# AnalogSigCond.net
KiCad netlist of a schematic drawn in Altium Designer
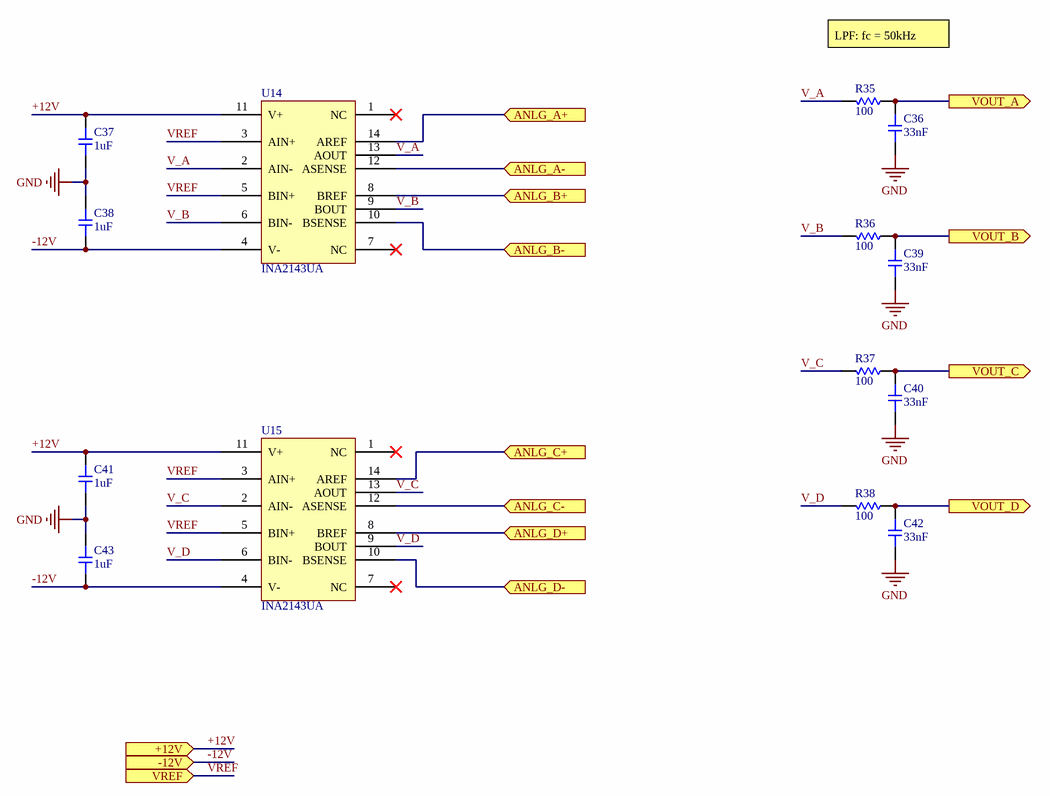
[diagram p0: AnalogSigCond.SchDoc]

(export (version "E")
  (design (tool "Eeschema 10.0.6"))
  (components
    (comp (ref "C36")
      (value "33nF")
      (footprint "AMDC:0603-CAP")
      (description "Capacitor")
      (libsource (lib "AMDC") (part "Capacitor"))
    )
    (comp (ref "C37")
      (value "1uF")
      (footprint "AMDC:0603-CAP")
      (description "Capacitor")
      (libsource (lib "AMDC") (part "Capacitor"))
    )
    (comp (ref "C38")
      (value "1uF")
      (footprint "AMDC:0603-CAP")
      (description "Capacitor")
      (libsource (lib "AMDC") (part "Capacitor"))
    )
    (comp (ref "C39")
      (value "33nF")
      (footprint "AMDC:0603-CAP")
      (description "Capacitor")
      (libsource (lib "AMDC") (part "Capacitor"))
    )
    (comp (ref "C40")
      (value "33nF")
      (footprint "AMDC:0603-CAP")
      (description "Capacitor")
      (libsource (lib "AMDC") (part "Capacitor"))
    )
    (comp (ref "C41")
      (value "1uF")
      (footprint "AMDC:0603-CAP")
      (description "Capacitor")
      (libsource (lib "AMDC") (part "Capacitor"))
    )
    (comp (ref "C42")
      (value "33nF")
      (footprint "AMDC:0603-CAP")
      (description "Capacitor")
      (libsource (lib "AMDC") (part "Capacitor"))
    )
    (comp (ref "C43")
      (value "1uF")
      (footprint "AMDC:0603-CAP")
      (description "Capacitor")
      (libsource (lib "AMDC") (part "Capacitor"))
    )
    (comp (ref "R35")
      (value "100")
      (footprint "AMDC:0603-RES")
      (description "Resistor")
      (libsource (lib "AMDC") (part "Resistor"))
    )
    (comp (ref "R36")
      (value "100")
      (footprint "AMDC:0603-RES")
      (description "Resistor")
      (libsource (lib "AMDC") (part "Resistor"))
    )
    (comp (ref "R37")
      (value "100")
      (footprint "AMDC:0603-RES")
      (description "Resistor")
      (libsource (lib "AMDC") (part "Resistor"))
    )
    (comp (ref "R38")
      (value "100")
      (footprint "AMDC:0603-RES")
      (description "Resistor")
      (libsource (lib "AMDC") (part "Resistor"))
    )
    (comp (ref "U14")
      (value "INA2143UA")
      (footprint "AMDC:SOIC127P600X175-14N")
      (description "IC OPAMP DIFF 150KHZ 14SOIC")
      (libsource (lib "AMDC") (part "INA2143UA"))
    )
    (comp (ref "U15")
      (value "INA2143UA")
      (footprint "AMDC:SOIC127P600X175-14N")
      (description "IC OPAMP DIFF 150KHZ 14SOIC")
      (libsource (lib "AMDC") (part "INA2143UA"))
    )
  )
  (nets
    (net (code "1") (name "/+12V") (class "Default")
      (node (ref "C37") (pin "2") (pinfunction "2_2") (pintype "passive"))
      (node (ref "C41") (pin "2") (pinfunction "2_2") (pintype "passive"))
      (node (ref "U14") (pin "11") (pinfunction "V+_11") (pintype "passive"))
      (node (ref "U15") (pin "11") (pinfunction "V+_11") (pintype "passive"))
    )
    (net (code "2") (name "/-12V") (class "Default")
      (node (ref "C38") (pin "1") (pinfunction "1_1") (pintype "passive"))
      (node (ref "C43") (pin "1") (pinfunction "1_1") (pintype "passive"))
      (node (ref "U14") (pin "4") (pinfunction "V-_4") (pintype "passive"))
      (node (ref "U15") (pin "4") (pinfunction "V-_4") (pintype "passive"))
    )
    (net (code "3") (name "/ANLG_A+") (class "Default")
      (node (ref "U14") (pin "14") (pinfunction "AREF_14") (pintype "passive"))
    )
    (net (code "4") (name "/ANLG_A-") (class "Default")
      (node (ref "U14") (pin "12") (pinfunction "ASENSE_12") (pintype "passive"))
    )
    (net (code "5") (name "/ANLG_B+") (class "Default")
      (node (ref "U14") (pin "8") (pinfunction "BREF_8") (pintype "passive"))
    )
    (net (code "6") (name "/ANLG_B-") (class "Default")
      (node (ref "U14") (pin "10") (pinfunction "BSENSE_10") (pintype "passive"))
    )
    (net (code "7") (name "/ANLG_C+") (class "Default")
      (node (ref "U15") (pin "14") (pinfunction "AREF_14") (pintype "passive"))
    )
    (net (code "8") (name "/ANLG_C-") (class "Default")
      (node (ref "U15") (pin "12") (pinfunction "ASENSE_12") (pintype "passive"))
    )
    (net (code "9") (name "/ANLG_D+") (class "Default")
      (node (ref "U15") (pin "8") (pinfunction "BREF_8") (pintype "passive"))
    )
    (net (code "10") (name "/ANLG_D-") (class "Default")
      (node (ref "U15") (pin "10") (pinfunction "BSENSE_10") (pintype "passive"))
    )
    (net (code "11") (name "/VOUT_A") (class "Default")
      (node (ref "C36") (pin "1") (pinfunction "1_1") (pintype "passive"))
      (node (ref "R35") (pin "1") (pinfunction "1_1") (pintype "passive"))
    )
    (net (code "12") (name "/VOUT_B") (class "Default")
      (node (ref "C39") (pin "1") (pinfunction "1_1") (pintype "passive"))
      (node (ref "R36") (pin "1") (pinfunction "1_1") (pintype "passive"))
    )
    (net (code "13") (name "/VOUT_C") (class "Default")
      (node (ref "C40") (pin "1") (pinfunction "1_1") (pintype "passive"))
      (node (ref "R37") (pin "1") (pinfunction "1_1") (pintype "passive"))
    )
    (net (code "14") (name "/VOUT_D") (class "Default")
      (node (ref "C42") (pin "1") (pinfunction "1_1") (pintype "passive"))
      (node (ref "R38") (pin "1") (pinfunction "1_1") (pintype "passive"))
    )
    (net (code "15") (name "/VREF") (class "Default")
      (node (ref "U14") (pin "3") (pinfunction "AIN+_3") (pintype "passive"))
      (node (ref "U14") (pin "5") (pinfunction "BIN+_5") (pintype "passive"))
      (node (ref "U15") (pin "3") (pinfunction "AIN+_3") (pintype "passive"))
      (node (ref "U15") (pin "5") (pinfunction "BIN+_5") (pintype "passive"))
    )
    (net (code "16") (name "/V_A") (class "Default")
      (node (ref "R35") (pin "2") (pinfunction "2_2") (pintype "passive"))
      (node (ref "U14") (pin "13") (pinfunction "AOUT_13") (pintype "passive"))
      (node (ref "U14") (pin "2") (pinfunction "AIN-_2") (pintype "passive"))
    )
    (net (code "17") (name "/V_B") (class "Default")
      (node (ref "R36") (pin "2") (pinfunction "2_2") (pintype "passive"))
      (node (ref "U14") (pin "6") (pinfunction "BIN-_6") (pintype "passive"))
      (node (ref "U14") (pin "9") (pinfunction "BOUT_9") (pintype "passive"))
    )
    (net (code "18") (name "/V_C") (class "Default")
      (node (ref "R37") (pin "2") (pinfunction "2_2") (pintype "passive"))
      (node (ref "U15") (pin "13") (pinfunction "AOUT_13") (pintype "passive"))
      (node (ref "U15") (pin "2") (pinfunction "AIN-_2") (pintype "passive"))
    )
    (net (code "19") (name "/V_D") (class "Default")
      (node (ref "R38") (pin "2") (pinfunction "2_2") (pintype "passive"))
      (node (ref "U15") (pin "6") (pinfunction "BIN-_6") (pintype "passive"))
      (node (ref "U15") (pin "9") (pinfunction "BOUT_9") (pintype "passive"))
    )
    (net (code "20") (name "GND") (class "Default")
      (node (ref "C36") (pin "2") (pinfunction "2_2") (pintype "passive"))
      (node (ref "C37") (pin "1") (pinfunction "1_1") (pintype "passive"))
      (node (ref "C38") (pin "2") (pinfunction "2_2") (pintype "passive"))
      (node (ref "C39") (pin "2") (pinfunction "2_2") (pintype "passive"))
      (node (ref "C40") (pin "2") (pinfunction "2_2") (pintype "passive"))
      (node (ref "C41") (pin "1") (pinfunction "1_1") (pintype "passive"))
      (node (ref "C42") (pin "2") (pinfunction "2_2") (pintype "passive"))
      (node (ref "C43") (pin "2") (pinfunction "2_2") (pintype "passive"))
    )
    (net (code "21") (name "unconnected-(U14-NC-Pad1)") (class "Default")
      (node (ref "U14") (pin "1") (pinfunction "NC_1") (pintype "passive+no_connect"))
    )
    (net (code "22") (name "unconnected-(U14-NC-Pad7)") (class "Default")
      (node (ref "U14") (pin "7") (pinfunction "NC_7") (pintype "passive+no_connect"))
    )
    (net (code "23") (name "unconnected-(U15-NC-Pad1)") (class "Default")
      (node (ref "U15") (pin "1") (pinfunction "NC_1") (pintype "passive+no_connect"))
    )
    (net (code "24") (name "unconnected-(U15-NC-Pad7)") (class "Default")
      (node (ref "U15") (pin "7") (pinfunction "NC_7") (pintype "passive+no_connect"))
    )
  )
)
